# 5VBoost.net
KiCad netlist of a schematic drawn in Altium Designer
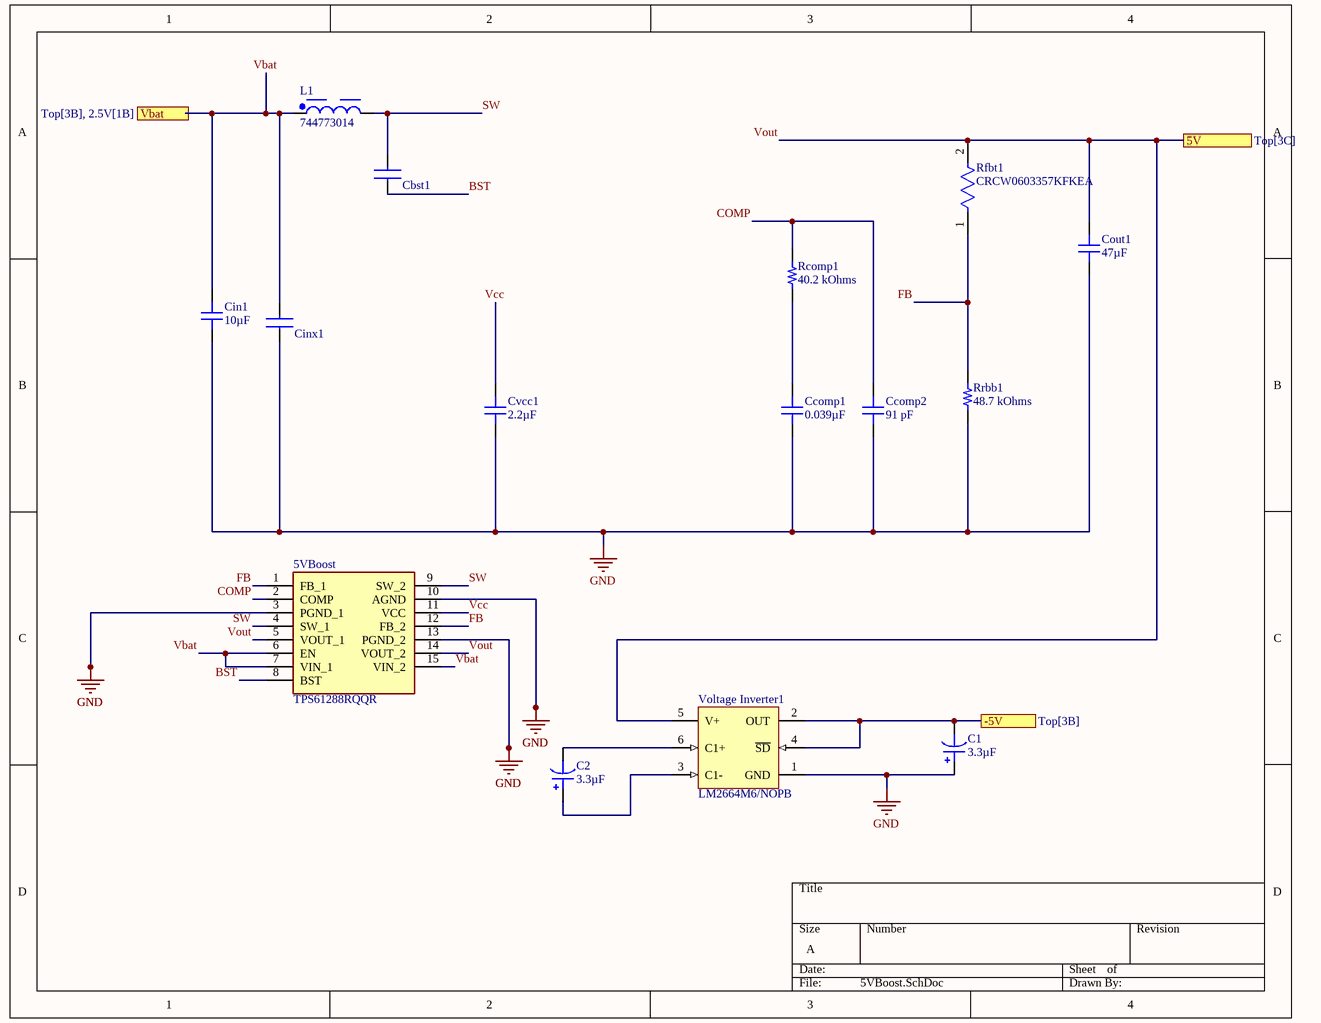
[diagram p0: 5VBoost.SchDoc]

(export (version "E")
  (design (tool "Eeschema 10.0.6"))
  (components
    (comp (ref "5VBoost")
      (value "TPS61288RQQR")
      (footprint "SamacSys:TPS61288RQQR")
      (description "Integrated Circuit")
      (fields (field (name "MOUSER PART NUMBER") "595-TPS61288RQQR"))
      (libsource (lib "*") (part "TPS61288RQQR"))
    )
    (comp (ref "C1")
      (value "3.3µF")
      (footprint "CAP POL 1411_3528")
      (description "CAP-TANT SM 3.3UF 16V")
      (fields (field (name "TOLERANCE") "±10%") (field (name "PART NUMBER") "SCTB335K16"))
      (libsource (lib "Gopher Motorsports") (part "POLARISED CAPACITOR"))
    )
    (comp (ref "C2")
      (value "3.3µF")
      (footprint "CAP POL 1411_3528")
      (description "CAP-TANT SM 3.3UF 16V")
      (fields (field (name "TOLERANCE") "±10%") (field (name "PART NUMBER") "SCTB335K16"))
      (libsource (lib "Gopher Motorsports") (part "POLARISED CAPACITOR"))
    )
    (comp (ref "Cbst1")
      (value "Capacitor 100nF 0603")
      (footprint "CAPC1608X90N")
      (fields
        (field (name "MANUFACTURER_PART_NUMBER") "CGA3E2X7R1H104K080AA")
        (field (name "MOUSER2 PART NUMBER") "810-CGA3E2X7R1H104K")
      )
      (libsource (lib "Gopher Motorsports") (part "CGA3E2X7R1H104K080AA"))
    )
    (comp (ref "Ccomp1")
      (value "0.039µF")
      (footprint "CAP 0603_1608")
      (description "CAP CER 0.039UF 50V X7R 0603")
      (fields (field (name "MANUFACTURER") "AVX Corporation") (field (name "PART NUMBER") "06035C393JAT2A"))
      (libsource (lib "Gopher Motorsports") (part "CAPACITOR"))
    )
    (comp (ref "Ccomp2")
      (value "91 pF")
      (footprint "CAP 0603_1608")
      (description "CAP CER 91PF 100V C0G/NP0 0603")
      (fields (field (name "MANUFACTURER") "KEMET") (field (name "TOLERANCE") "±5%"))
      (libsource (lib "Gopher Motorsports") (part "CAPACITOR"))
    )
    (comp (ref "Cin1")
      (value "10µF")
      (footprint "CAP 0603_1608")
      (description "CAP CER 10UF 6.3V X5R 0603")
      (fields (field (name "PART NUMBER") "06036D106KAT2A") (field (name "TOLERANCE") "±10%"))
      (libsource (lib "Gopher Motorsports") (part "CAPACITOR"))
    )
    (comp (ref "Cinx1")
      (value "Capacitor 100nF 0603")
      (footprint "CAPC1608X90N")
      (fields
        (field (name "MANUFACTURER_PART_NUMBER") "CGA3E2X7R1H104K080AA")
        (field (name "MOUSER2 PART NUMBER") "810-CGA3E2X7R1H104K")
      )
      (libsource (lib "Gopher Motorsports") (part "CGA3E2X7R1H104K080AA"))
    )
    (comp (ref "Cout1")
      (value "47µF")
      (footprint "CAP 0603_1608")
      (description "CAP CER 47UF 6.3V X5R 0603")
      (fields (field (name "TOLERANCE") "±20%") (field (name "MANUFACTURER") "AVX Corporation"))
      (libsource (lib "Gopher Motorsports") (part "CAPACITOR"))
    )
    (comp (ref "Cvcc1")
      (value "2.2µF")
      (footprint "CAP 0603_1608")
      (description "CAP CER 2.2UF 16V X5R 0603")
      (fields (field (name "MANUFACTURER") "AVX Corporation") (field (name "PART NUMBER") "0603YD225KAT2A"))
      (libsource (lib "Gopher Motorsports") (part "CAPACITOR"))
    )
    (comp (ref "L1")
      (value "744773014")
      (footprint "WE-PD2_4532")
      (fields (field (name "TOLERANCE") "20%"))
      (libsource (lib "Altium Content Vault") (part "Inductor - 2"))
    )
    (comp (ref "Rcomp1")
      (value "40.2 kOhms")
      (footprint "RES 0603_1608")
      (description "RES SMD 40.2KOHM 0.5% 1/10W 0603")
      (fields (field (name "PART NUMBER") "RT0603DRE0740K2L") (field (name "TOLERANCE") "±0.5%"))
      (libsource (lib "Gopher Motorsports") (part "RESISTOR"))
    )
    (comp (ref "Rfbt1")
      (value "CRCW0603357KFKEA")
      (footprint "FP-CRCW0603-e3-IPC_C")
      (description "RES Thick Film, 357kΩ, 1%, 0.1W, 100ppm/°C, 0603")
      (fields (field (name "TOLERANCE") "1%"))
      (libsource (lib "Altium Content Vault") (part "1029c3af85768c4190bb7ad29bc67b5"))
    )
    (comp (ref "Rrbb1")
      (value "48.7 kOhms")
      (footprint "RES 0603_1608")
      (description "RES SMD 48.7K OHM 1% 1/16W 0603")
      (fields
        (field (name "MANUFACTURER") "TE Connectivity Passive Product")
        (field (name "TOLERANCE") "±1%")
      )
      (libsource (lib "Gopher Motorsports") (part "RESISTOR"))
    )
    (comp (ref "Voltage Inverter1")
      (value "LM2664M6/NOPB")
      (footprint "DBV0006A_L")
      (description "Switched Capacitor Voltage Converter, 6-pin SOT-23, Pb-Free")
      (fields (field (name "MANUFACTURER") "Texas Instruments"))
      (libsource (lib "Altium Content Vault") (part "PM-CHP-LM2664M6-6"))
    )
  )
  (nets
    (net (code "1") (name "/-5V") (class "Default")
      (node (ref "C1") (pin "2") (pinfunction "2_2") (pintype "passive"))
      (node (ref "Voltage Inverter1") (pin "2") (pinfunction "OUT_2") (pintype "power_in"))
      (node (ref "Voltage Inverter1") (pin "4") (pinfunction "~{SD}_4") (pintype "input"))
    )
    (net (code "2") (name "/BST") (class "Default")
      (node (ref "5VBoost") (pin "8") (pinfunction "BST_8") (pintype "passive"))
      (node (ref "Cbst1") (pin "1") (pinfunction "1_1") (pintype "passive"))
    )
    (net (code "3") (name "/COMP") (class "Default")
      (node (ref "5VBoost") (pin "2") (pinfunction "COMP_2") (pintype "passive"))
      (node (ref "Ccomp2") (pin "2") (pinfunction "2_2") (pintype "passive"))
      (node (ref "Rcomp1") (pin "2") (pinfunction "2_2") (pintype "passive"))
    )
    (net (code "4") (name "/FB") (class "Default")
      (node (ref "5VBoost") (pin "1") (pinfunction "FB_1_1") (pintype "passive"))
      (node (ref "5VBoost") (pin "12") (pinfunction "FB_2_12") (pintype "passive"))
      (node (ref "Rfbt1") (pin "1") (pinfunction "1_1") (pintype "passive"))
      (node (ref "Rrbb1") (pin "2") (pinfunction "2_2") (pintype "passive"))
    )
    (net (code "5") (name "/SW") (class "Default")
      (node (ref "5VBoost") (pin "4") (pinfunction "SW_1_4") (pintype "passive"))
      (node (ref "5VBoost") (pin "9") (pinfunction "SW_2_9") (pintype "passive"))
      (node (ref "Cbst1") (pin "2") (pinfunction "2_2") (pintype "passive"))
      (node (ref "L1") (pin "2") (pinfunction "2_2") (pintype "passive"))
    )
    (net (code "6") (name "/Vbat") (class "Default")
      (node (ref "5VBoost") (pin "15") (pinfunction "VIN_2_15") (pintype "passive"))
      (node (ref "5VBoost") (pin "6") (pinfunction "EN_6") (pintype "passive"))
      (node (ref "5VBoost") (pin "7") (pinfunction "VIN_1_7") (pintype "passive"))
      (node (ref "Cin1") (pin "2") (pinfunction "2_2") (pintype "passive"))
      (node (ref "Cinx1") (pin "2") (pinfunction "2_2") (pintype "passive"))
      (node (ref "L1") (pin "1") (pinfunction "1_1") (pintype "passive"))
    )
    (net (code "7") (name "/Vcc") (class "Default")
      (node (ref "5VBoost") (pin "11") (pinfunction "VCC_11") (pintype "passive"))
      (node (ref "Cvcc1") (pin "2") (pinfunction "2_2") (pintype "passive"))
    )
    (net (code "8") (name "/Vout") (class "Default")
      (node (ref "5VBoost") (pin "14") (pinfunction "VOUT_2_14") (pintype "passive"))
      (node (ref "5VBoost") (pin "5") (pinfunction "VOUT_1_5") (pintype "passive"))
      (node (ref "Cout1") (pin "2") (pinfunction "2_2") (pintype "passive"))
      (node (ref "Rfbt1") (pin "2") (pinfunction "2_2") (pintype "passive"))
      (node (ref "Voltage Inverter1") (pin "5") (pinfunction "V+_5") (pintype "power_in"))
    )
    (net (code "9") (name "GND") (class "Default")
      (node (ref "5VBoost") (pin "10") (pinfunction "AGND_10") (pintype "passive"))
      (node (ref "5VBoost") (pin "13") (pinfunction "PGND_2_13") (pintype "passive"))
      (node (ref "5VBoost") (pin "3") (pinfunction "PGND_1_3") (pintype "passive"))
      (node (ref "C1") (pin "1") (pinfunction "1_1") (pintype "passive"))
      (node (ref "Ccomp1") (pin "1") (pinfunction "1_1") (pintype "passive"))
      (node (ref "Ccomp2") (pin "1") (pinfunction "1_1") (pintype "passive"))
      (node (ref "Cin1") (pin "1") (pinfunction "1_1") (pintype "passive"))
      (node (ref "Cinx1") (pin "1") (pinfunction "1_1") (pintype "passive"))
      (node (ref "Cout1") (pin "1") (pinfunction "1_1") (pintype "passive"))
      (node (ref "Cvcc1") (pin "1") (pinfunction "1_1") (pintype "passive"))
      (node (ref "Rrbb1") (pin "1") (pinfunction "1_1") (pintype "passive"))
      (node (ref "Voltage Inverter1") (pin "1") (pinfunction "GND_1") (pintype "power_in"))
    )
    (net (code "10") (name "Net-(Ccomp1-Pad2)") (class "Default")
      (node (ref "Ccomp1") (pin "2") (pinfunction "2_2") (pintype "passive"))
      (node (ref "Rcomp1") (pin "1") (pinfunction "1_1") (pintype "passive"))
    )
    (net (code "11") (name "Net-(Voltage Inverter1-C1+)") (class "Default")
      (node (ref "C2") (pin "2") (pinfunction "2_2") (pintype "passive"))
      (node (ref "Voltage Inverter1") (pin "6") (pinfunction "C1+_6") (pintype "input"))
    )
    (net (code "12") (name "Net-(Voltage Inverter1-C1-)") (class "Default")
      (node (ref "C2") (pin "1") (pinfunction "1_1") (pintype "passive"))
      (node (ref "Voltage Inverter1") (pin "3") (pinfunction "C1-_3") (pintype "input"))
    )
  )
)
